# HDC1080.net
KiCad netlist of a schematic drawn in Altium Designer
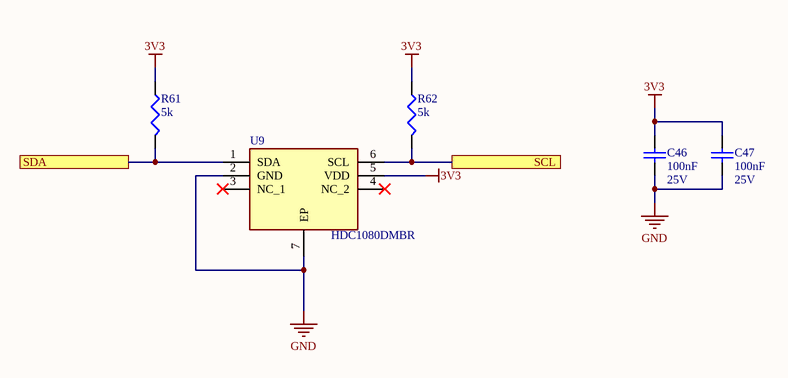
[diagram p0: HDC1080.SchDoc]

(export (version "E")
  (design (tool "Eeschema 10.0.6"))
  (components
    (comp (ref "C46")
      (value "100nF")
      (footprint "VESC_BMS:C0402")
      (description "Capacitor, 100nF, 25V, X7R")
      (fields (field (name "VOLTAGE RATING") "25V"))
      (libsource (lib "AR_Capacitors_Ceramic") (part "100nF/0402/CER/25V"))
    )
    (comp (ref "C47")
      (value "100nF")
      (footprint "VESC_BMS:C0402")
      (description "Capacitor, 100nF, 25V, X7R")
      (fields (field (name "VOLTAGE RATING") "25V"))
      (libsource (lib "AR_Capacitors_Ceramic") (part "100nF/0402/CER/25V"))
    )
    (comp (ref "R61")
      (value "5k")
      (footprint "VESC_BMS:0402")
      (description "Resistor, 10k, 0.1%, 0.0625W, 50V, 100PPM, 0402")
      (libsource (lib "AR_Resistors_SMD") (part "10k/0402/0063W/50V"))
    )
    (comp (ref "R62")
      (value "5k")
      (footprint "VESC_BMS:0402")
      (description "Resistor, 10k, 0.1%, 0.0625W, 50V, 100PPM, 0402")
      (libsource (lib "AR_Resistors_SMD") (part "10k/0402/0063W/50V"))
    )
    (comp (ref "U9")
      (value "HDC1080DMBR")
      (footprint "SON100P300X300X80-7N-D")
      (description "Integrated Circuit")
      (fields (field (name "MOUSER PART NUMBER") "595-HDC1080DMBR"))
      (libsource (lib "VESC_BMS") (part "HDC1080DMBR"))
    )
  )
  (nets
    (net (code "1") (name "/SCL") (class "Default")
      (node (ref "R62") (pin "1") (pinfunction "1_1") (pintype "passive"))
      (node (ref "U9") (pin "6") (pinfunction "SCL_6") (pintype "passive"))
    )
    (net (code "2") (name "/SDA") (class "Default")
      (node (ref "R61") (pin "1") (pinfunction "1_1") (pintype "passive"))
      (node (ref "U9") (pin "1") (pinfunction "SDA_1") (pintype "passive"))
    )
    (net (code "3") (name "3V3") (class "Default")
      (node (ref "C46") (pin "2") (pinfunction "2_2") (pintype "passive"))
      (node (ref "C47") (pin "2") (pinfunction "2_2") (pintype "passive"))
      (node (ref "R61") (pin "2") (pinfunction "2_2") (pintype "passive"))
      (node (ref "R62") (pin "2") (pinfunction "2_2") (pintype "passive"))
      (node (ref "U9") (pin "5") (pinfunction "VDD_5") (pintype "passive"))
    )
    (net (code "4") (name "GND") (class "Default")
      (node (ref "C46") (pin "1") (pinfunction "1_1") (pintype "passive"))
      (node (ref "C47") (pin "1") (pinfunction "1_1") (pintype "passive"))
      (node (ref "U9") (pin "2") (pinfunction "GND_2") (pintype "passive"))
      (node (ref "U9") (pin "7") (pinfunction "EP_7") (pintype "passive"))
    )
    (net (code "5") (name "unconnected-(U9-NC_1-Pad3)") (class "Default")
      (node (ref "U9") (pin "3") (pinfunction "NC_1_3") (pintype "passive+no_connect"))
    )
    (net (code "6") (name "unconnected-(U9-NC_2-Pad4)") (class "Default")
      (node (ref "U9") (pin "4") (pinfunction "NC_2_4") (pintype "passive+no_connect"))
    )
  )
)
